# PISO2sch.net
KiCad netlist of a schematic drawn in EAGLE
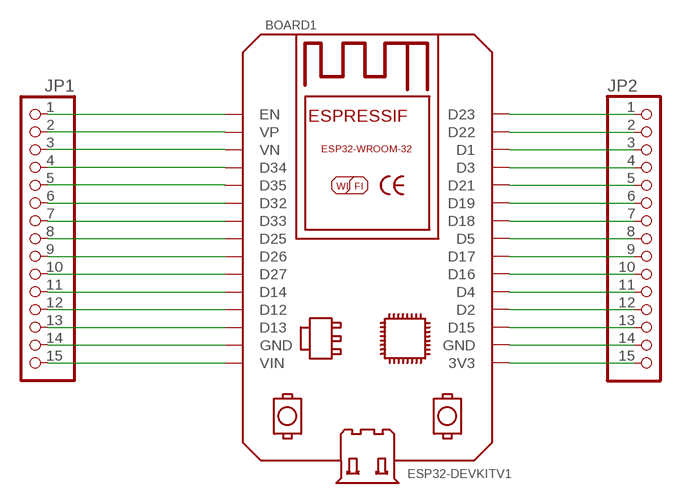
[diagram p0: schematic, sheet 1]

(export (version "E")
  (design (tool "Eeschema 10.0.6"))
  (components
    (comp (ref "BOARD1")
      (value "ESP32DEVKITV1")
      (footprint "eagle-import:ESP32-DEVKITV1")
      (libsource (lib "eagle-import") (part "ESP32DEVKITV1"))
    )
    (comp (ref "JP1")
      (value "PINHD-1X15")
      (footprint "eagle-import:1X15")
      (libsource (lib "eagle-import") (part "PINHD-1X15"))
    )
    (comp (ref "JP2")
      (value "PINHD-1X15")
      (footprint "eagle-import:1X15")
      (libsource (lib "eagle-import") (part "PINHD-1X15"))
    )
  )
  (nets
    (net (code "1") (name "Net-(BOARD1-GND-PadGND@1)") (class "Default")
      (node (ref "BOARD1") (pin "GND@1") (pinfunction "GND_GND@1") (pintype "bidirectional"))
      (node (ref "JP2") (pin "14") (pinfunction "14_14") (pintype "passive"))
    )
    (net (code "2") (name "Net-(BOARD1-Pad3V3)") (class "Default")
      (node (ref "BOARD1") (pin "3V3") (pinfunction "3V3_3V3") (pintype "bidirectional"))
      (node (ref "JP2") (pin "15") (pinfunction "15_15") (pintype "passive"))
    )
    (net (code "3") (name "Net-(BOARD1-PadD1)") (class "Default")
      (node (ref "BOARD1") (pin "D1") (pinfunction "D1_D1") (pintype "bidirectional"))
      (node (ref "JP2") (pin "3") (pinfunction "3_3") (pintype "passive"))
    )
    (net (code "4") (name "Net-(BOARD1-PadD2)") (class "Default")
      (node (ref "BOARD1") (pin "D2") (pinfunction "D2_D2") (pintype "bidirectional"))
      (node (ref "JP2") (pin "12") (pinfunction "12_12") (pintype "passive"))
    )
    (net (code "5") (name "Net-(BOARD1-PadD3)") (class "Default")
      (node (ref "BOARD1") (pin "D3") (pinfunction "D3_D3") (pintype "bidirectional"))
      (node (ref "JP2") (pin "4") (pinfunction "4_4") (pintype "passive"))
    )
    (net (code "6") (name "Net-(BOARD1-PadD4)") (class "Default")
      (node (ref "BOARD1") (pin "D4") (pinfunction "D4_D4") (pintype "bidirectional"))
      (node (ref "JP2") (pin "11") (pinfunction "11_11") (pintype "passive"))
    )
    (net (code "7") (name "Net-(BOARD1-PadD5)") (class "Default")
      (node (ref "BOARD1") (pin "D5") (pinfunction "D5_D5") (pintype "bidirectional"))
      (node (ref "JP2") (pin "8") (pinfunction "8_8") (pintype "passive"))
    )
    (net (code "8") (name "Net-(BOARD1-PadD12)") (class "Default")
      (node (ref "BOARD1") (pin "D12") (pinfunction "D12_D12") (pintype "bidirectional"))
      (node (ref "JP1") (pin "12") (pinfunction "12_12") (pintype "passive"))
    )
    (net (code "9") (name "Net-(BOARD1-PadD13)") (class "Default")
      (node (ref "BOARD1") (pin "D13") (pinfunction "D13_D13") (pintype "bidirectional"))
      (node (ref "JP1") (pin "13") (pinfunction "13_13") (pintype "passive"))
    )
    (net (code "10") (name "Net-(BOARD1-PadD14)") (class "Default")
      (node (ref "BOARD1") (pin "D14") (pinfunction "D14_D14") (pintype "bidirectional"))
      (node (ref "JP1") (pin "11") (pinfunction "11_11") (pintype "passive"))
    )
    (net (code "11") (name "Net-(BOARD1-PadD15)") (class "Default")
      (node (ref "BOARD1") (pin "D15") (pinfunction "D15_D15") (pintype "bidirectional"))
      (node (ref "JP2") (pin "13") (pinfunction "13_13") (pintype "passive"))
    )
    (net (code "12") (name "Net-(BOARD1-PadD16)") (class "Default")
      (node (ref "BOARD1") (pin "D16") (pinfunction "D16_D16") (pintype "bidirectional"))
      (node (ref "JP2") (pin "10") (pinfunction "10_10") (pintype "passive"))
    )
    (net (code "13") (name "Net-(BOARD1-PadD17)") (class "Default")
      (node (ref "BOARD1") (pin "D17") (pinfunction "D17_D17") (pintype "bidirectional"))
      (node (ref "JP2") (pin "9") (pinfunction "9_9") (pintype "passive"))
    )
    (net (code "14") (name "Net-(BOARD1-PadD18)") (class "Default")
      (node (ref "BOARD1") (pin "D18") (pinfunction "D18_D18") (pintype "bidirectional"))
      (node (ref "JP2") (pin "7") (pinfunction "7_7") (pintype "passive"))
    )
    (net (code "15") (name "Net-(BOARD1-PadD19)") (class "Default")
      (node (ref "BOARD1") (pin "D19") (pinfunction "D19_D19") (pintype "bidirectional"))
      (node (ref "JP2") (pin "6") (pinfunction "6_6") (pintype "passive"))
    )
    (net (code "16") (name "Net-(BOARD1-PadD21)") (class "Default")
      (node (ref "BOARD1") (pin "D21") (pinfunction "D21_D21") (pintype "bidirectional"))
      (node (ref "JP2") (pin "5") (pinfunction "5_5") (pintype "passive"))
    )
    (net (code "17") (name "Net-(BOARD1-PadD22)") (class "Default")
      (node (ref "BOARD1") (pin "D22") (pinfunction "D22_D22") (pintype "bidirectional"))
      (node (ref "JP2") (pin "2") (pinfunction "2_2") (pintype "passive"))
    )
    (net (code "18") (name "Net-(BOARD1-PadD23)") (class "Default")
      (node (ref "BOARD1") (pin "D23") (pinfunction "D23_D23") (pintype "bidirectional"))
      (node (ref "JP2") (pin "1") (pinfunction "1_1") (pintype "passive"))
    )
    (net (code "19") (name "Net-(BOARD1-PadD25)") (class "Default")
      (node (ref "BOARD1") (pin "D25") (pinfunction "D25_D25") (pintype "bidirectional"))
      (node (ref "JP1") (pin "8") (pinfunction "8_8") (pintype "passive"))
    )
    (net (code "20") (name "Net-(BOARD1-PadD26)") (class "Default")
      (node (ref "BOARD1") (pin "D26") (pinfunction "D26_D26") (pintype "bidirectional"))
      (node (ref "JP1") (pin "9") (pinfunction "9_9") (pintype "passive"))
    )
    (net (code "21") (name "Net-(BOARD1-PadD27)") (class "Default")
      (node (ref "BOARD1") (pin "D27") (pinfunction "D27_D27") (pintype "bidirectional"))
      (node (ref "JP1") (pin "10") (pinfunction "10_10") (pintype "passive"))
    )
    (net (code "22") (name "Net-(BOARD1-PadD32)") (class "Default")
      (node (ref "BOARD1") (pin "D32") (pinfunction "D32_D32") (pintype "bidirectional"))
      (node (ref "JP1") (pin "6") (pinfunction "6_6") (pintype "passive"))
    )
    (net (code "23") (name "Net-(BOARD1-PadD33)") (class "Default")
      (node (ref "BOARD1") (pin "D33") (pinfunction "D33_D33") (pintype "bidirectional"))
      (node (ref "JP1") (pin "7") (pinfunction "7_7") (pintype "passive"))
    )
    (net (code "24") (name "Net-(BOARD1-PadD34)") (class "Default")
      (node (ref "BOARD1") (pin "D34") (pinfunction "D34_D34") (pintype "bidirectional"))
      (node (ref "JP1") (pin "4") (pinfunction "4_4") (pintype "passive"))
    )
    (net (code "25") (name "Net-(BOARD1-PadD35)") (class "Default")
      (node (ref "BOARD1") (pin "D35") (pinfunction "D35_D35") (pintype "bidirectional"))
      (node (ref "JP1") (pin "5") (pinfunction "5_5") (pintype "passive"))
    )
    (net (code "26") (name "Net-(BOARD1-PadEN)") (class "Default")
      (node (ref "BOARD1") (pin "EN") (pinfunction "EN_EN") (pintype "bidirectional"))
      (node (ref "JP1") (pin "1") (pinfunction "1_1") (pintype "passive"))
    )
    (net (code "27") (name "Net-(BOARD1-PadGND)") (class "Default")
      (node (ref "BOARD1") (pin "GND") (pinfunction "GND_GND") (pintype "bidirectional"))
      (node (ref "JP1") (pin "14") (pinfunction "14_14") (pintype "passive"))
    )
    (net (code "28") (name "Net-(BOARD1-PadVIN)") (class "Default")
      (node (ref "BOARD1") (pin "VIN") (pinfunction "VIN_VIN") (pintype "bidirectional"))
      (node (ref "JP1") (pin "15") (pinfunction "15_15") (pintype "passive"))
    )
    (net (code "29") (name "Net-(BOARD1-PadVN)") (class "Default")
      (node (ref "BOARD1") (pin "VN") (pinfunction "VN_VN") (pintype "bidirectional"))
      (node (ref "JP1") (pin "3") (pinfunction "3_3") (pintype "passive"))
    )
    (net (code "30") (name "Net-(BOARD1-PadVP)") (class "Default")
      (node (ref "BOARD1") (pin "VP") (pinfunction "VP_VP") (pintype "bidirectional"))
      (node (ref "JP1") (pin "2") (pinfunction "2_2") (pintype "passive"))
    )
  )
)
